# Sheet1.net
KiCad netlist of a schematic drawn in Altium Designer
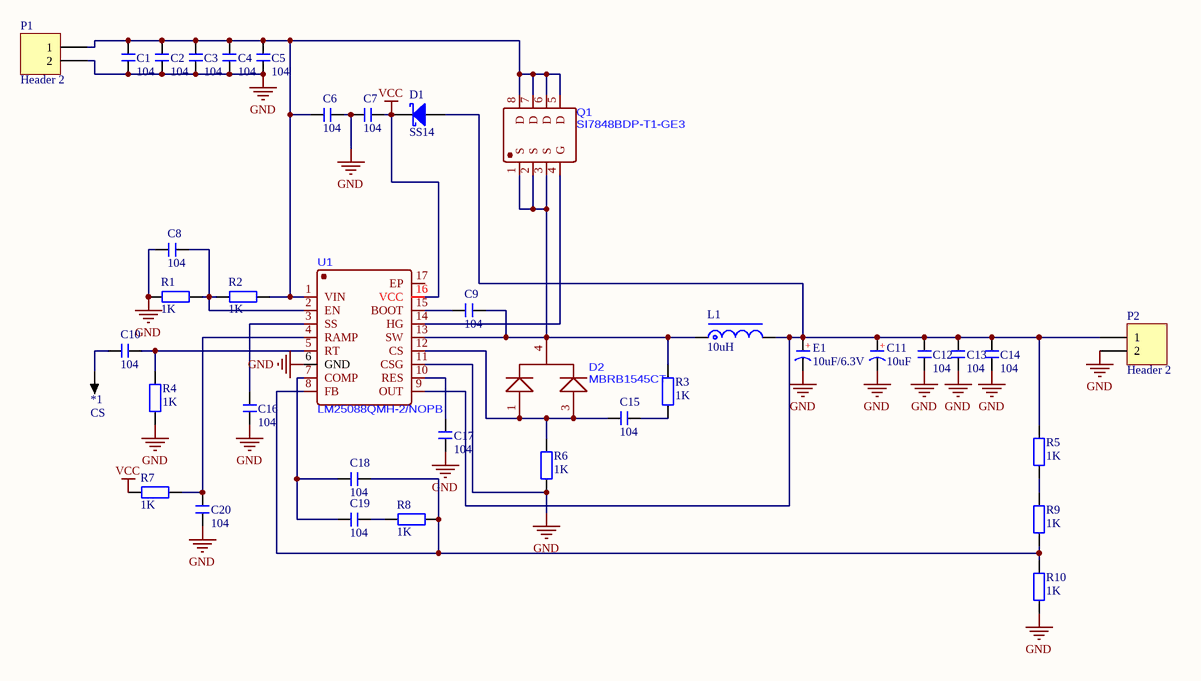
[diagram p0: Sheet1.SchDoc]

(export (version "E")
  (design (tool "Eeschema 10.0.6"))
  (components
    (comp (ref "*1")
      (value "CS")
      (footprint "R100")
      (description "探针焊盘")
      (libsource (lib "10 - 未分类元器件") (part "CS"))
    )
    (comp (ref "C1")
      (value "104")
      (footprint "C 0805_L")
      (description "贴片电容")
      (libsource (lib "01 - 电容-电阻-电感") (part "C"))
    )
    (comp (ref "C2")
      (value "104")
      (footprint "C 0805_L")
      (description "贴片电容")
      (libsource (lib "01 - 电容-电阻-电感") (part "C"))
    )
    (comp (ref "C3")
      (value "104")
      (footprint "C 0805_L")
      (description "贴片电容")
      (libsource (lib "01 - 电容-电阻-电感") (part "C"))
    )
    (comp (ref "C4")
      (value "104")
      (footprint "C 0805_L")
      (description "贴片电容")
      (libsource (lib "01 - 电容-电阻-电感") (part "C"))
    )
    (comp (ref "C5")
      (value "104")
      (footprint "C 0805_L")
      (description "贴片电容")
      (libsource (lib "01 - 电容-电阻-电感") (part "C"))
    )
    (comp (ref "C6")
      (value "104")
      (footprint "C 0805_L")
      (description "贴片电容")
      (libsource (lib "01 - 电容-电阻-电感") (part "C"))
    )
    (comp (ref "C7")
      (value "104")
      (footprint "C 0805_L")
      (description "贴片电容")
      (libsource (lib "01 - 电容-电阻-电感") (part "C"))
    )
    (comp (ref "C8")
      (value "104")
      (footprint "C 0805_L")
      (description "贴片电容")
      (libsource (lib "01 - 电容-电阻-电感") (part "C"))
    )
    (comp (ref "C9")
      (value "104")
      (footprint "C 0805_L")
      (description "贴片电容")
      (libsource (lib "01 - 电容-电阻-电感") (part "C"))
    )
    (comp (ref "C10")
      (value "104")
      (footprint "C 0805_L")
      (description "贴片电容")
      (libsource (lib "01 - 电容-电阻-电感") (part "C"))
    )
    (comp (ref "C11")
      (value "10uF")
      (footprint "CAP 3.5*8*11.5 - BK")
      (description "直插电解电容")
      (libsource (lib "01 - 电容-电阻-电感") (part "CE"))
    )
    (comp (ref "C12")
      (value "104")
      (footprint "C 0805_L")
      (description "贴片电容")
      (libsource (lib "01 - 电容-电阻-电感") (part "C"))
    )
    (comp (ref "C13")
      (value "104")
      (footprint "C 0805_L")
      (description "贴片电容")
      (libsource (lib "01 - 电容-电阻-电感") (part "C"))
    )
    (comp (ref "C14")
      (value "104")
      (footprint "C 0805_L")
      (description "贴片电容")
      (libsource (lib "01 - 电容-电阻-电感") (part "C"))
    )
    (comp (ref "C15")
      (value "104")
      (footprint "C 0805_L")
      (description "贴片电容")
      (libsource (lib "01 - 电容-电阻-电感") (part "C"))
    )
    (comp (ref "C16")
      (value "104")
      (footprint "C 0805_L")
      (description "贴片电容")
      (libsource (lib "01 - 电容-电阻-电感") (part "C"))
    )
    (comp (ref "C17")
      (value "104")
      (footprint "C 0805_L")
      (description "贴片电容")
      (libsource (lib "01 - 电容-电阻-电感") (part "C"))
    )
    (comp (ref "C18")
      (value "104")
      (footprint "C 0805_L")
      (description "贴片电容")
      (libsource (lib "01 - 电容-电阻-电感") (part "C"))
    )
    (comp (ref "C19")
      (value "104")
      (footprint "C 0805_L")
      (description "贴片电容")
      (libsource (lib "01 - 电容-电阻-电感") (part "C"))
    )
    (comp (ref "C20")
      (value "104")
      (footprint "C 0805_L")
      (description "贴片电容")
      (libsource (lib "01 - 电容-电阻-电感") (part "C"))
    )
    (comp (ref "D1")
      (value "SS14")
      (footprint "SMA")
      (description "肖特基二极管")
      (libsource (lib "02 - 二极管(LED)-三极管-整流桥") (part "SS14"))
    )
    (comp (ref "D2")
      (value "MBRB1545CT")
      (footprint "ONSC-D2PAK-3-418B-04_V")
      (libsource (lib "MBRB1545CT_2022-06-29") (part "MBRB1545CT"))
    )
    (comp (ref "E1")
      (value "10uF/6.3V")
      (footprint "CS 2.0*5*8 - C")
      (description "直插固态电容")
      (libsource (lib "01 - 电容-电阻-电感") (part "CS"))
    )
    (comp (ref "L1")
      (value "10uH")
      (footprint "CD31")
      (description "CD系列贴片线绕功率电感")
      (libsource (lib "01 - 电容-电阻-电感") (part "L-SMD"))
    )
    (comp (ref "P1")
      (value "Header 2")
      (footprint "HDR1X2")
      (description "Header, 2-Pin")
      (fields (field (name "PUBLISHER") "Altium Limited"))
      (libsource (lib "") (part "Header 2_1"))
    )
    (comp (ref "P2")
      (value "Header 2")
      (footprint "HDR1X2")
      (description "Header, 2-Pin")
      (fields (field (name "PUBLISHER") "Altium Limited"))
      (libsource (lib "Miscellaneous Connectors") (part "Header 2"))
    )
    (comp (ref "Q1")
      (value "SI7848BDP-T1-GE3")
      (footprint "POWERPAK-SO-8_L6.1-W5.1-P1.27-BL-EP")
      (libsource (lib "SI7848BDP-T1-GE3_2022-06-29") (part "SI7848BDP-T1-GE3"))
    )
    (comp (ref "R1")
      (value "1K")
      (footprint "R 0805_L")
      (description "贴片电阻")
      (libsource (lib "01 - 电容-电阻-电感") (part "R"))
    )
    (comp (ref "R2")
      (value "1K")
      (footprint "R 0805_L")
      (description "贴片电阻")
      (libsource (lib "01 - 电容-电阻-电感") (part "R"))
    )
    (comp (ref "R3")
      (value "1K")
      (footprint "R 0805_L")
      (description "贴片电阻")
      (libsource (lib "01 - 电容-电阻-电感") (part "R"))
    )
    (comp (ref "R4")
      (value "1K")
      (footprint "R 0805_L")
      (description "贴片电阻")
      (libsource (lib "01 - 电容-电阻-电感") (part "R"))
    )
    (comp (ref "R5")
      (value "1K")
      (footprint "R 0805_L")
      (description "贴片电阻")
      (libsource (lib "01 - 电容-电阻-电感") (part "R"))
    )
    (comp (ref "R6")
      (value "1K")
      (footprint "R 0805_L")
      (description "贴片电阻")
      (libsource (lib "01 - 电容-电阻-电感") (part "R"))
    )
    (comp (ref "R7")
      (value "1K")
      (footprint "R 0805_L")
      (description "贴片电阻")
      (libsource (lib "01 - 电容-电阻-电感") (part "R"))
    )
    (comp (ref "R8")
      (value "1K")
      (footprint "R 0805_L")
      (description "贴片电阻")
      (libsource (lib "01 - 电容-电阻-电感") (part "R"))
    )
    (comp (ref "R9")
      (value "1K")
      (footprint "R 0805_L")
      (description "贴片电阻")
      (libsource (lib "01 - 电容-电阻-电感") (part "R"))
    )
    (comp (ref "R10")
      (value "1K")
      (footprint "R 0805_L")
      (description "贴片电阻")
      (libsource (lib "01 - 电容-电阻-电感") (part "R"))
    )
    (comp (ref "U1")
      (value "LM25088QMH-2/NOPB")
      (footprint "HTSSOP-16_L5.0-W4.4-P0.65-LS6.4-BL-EP")
      (libsource (lib "PCB_Project") (part "LM25088QMH-2/NOPB"))
    )
  )
  (nets
    (net (code "1") (name "GND") (class "Default")
      (node (ref "C1") (pin "1") (pinfunction "1_1") (pintype "passive"))
      (node (ref "C11") (pin "2") (pinfunction "K_2") (pintype "passive"))
      (node (ref "C12") (pin "2") (pinfunction "2_2") (pintype "passive"))
      (node (ref "C13") (pin "2") (pinfunction "2_2") (pintype "passive"))
      (node (ref "C14") (pin "2") (pinfunction "2_2") (pintype "passive"))
      (node (ref "C16") (pin "2") (pinfunction "2_2") (pintype "passive"))
      (node (ref "C17") (pin "2") (pinfunction "2_2") (pintype "passive"))
      (node (ref "C2") (pin "1") (pinfunction "1_1") (pintype "passive"))
      (node (ref "C20") (pin "2") (pinfunction "2_2") (pintype "passive"))
      (node (ref "C3") (pin "1") (pinfunction "1_1") (pintype "passive"))
      (node (ref "C4") (pin "1") (pinfunction "1_1") (pintype "passive"))
      (node (ref "C5") (pin "1") (pinfunction "1_1") (pintype "passive"))
      (node (ref "C6") (pin "1") (pinfunction "1_1") (pintype "passive"))
      (node (ref "C7") (pin "2") (pinfunction "2_2") (pintype "passive"))
      (node (ref "C8") (pin "2") (pinfunction "2_2") (pintype "passive"))
      (node (ref "E1") (pin "2") (pinfunction "K_2") (pintype "passive"))
      (node (ref "P1") (pin "2") (pinfunction "2_2") (pintype "passive"))
      (node (ref "P2") (pin "2") (pinfunction "2_2") (pintype "passive"))
      (node (ref "R1") (pin "1") (pinfunction "1_1") (pintype "passive"))
      (node (ref "R10") (pin "1") (pinfunction "1_1") (pintype "passive"))
      (node (ref "R4") (pin "1") (pinfunction "1_1") (pintype "passive"))
      (node (ref "R6") (pin "1") (pinfunction "1_1") (pintype "passive"))
      (node (ref "U1") (pin "11") (pinfunction "CSG_11") (pintype "passive"))
      (node (ref "U1") (pin "6") (pinfunction "GND_6") (pintype "passive"))
    )
    (net (code "2") (name "Net-(*1-Pad1)") (class "Default")
      (node (ref "*1") (pin "1") (pinfunction "1_1") (pintype "passive"))
      (node (ref "C10") (pin "2") (pinfunction "2_2") (pintype "passive"))
    )
    (net (code "3") (name "Net-(C11-A)") (class "Default")
      (node (ref "C11") (pin "1") (pinfunction "A_1") (pintype "passive"))
      (node (ref "C12") (pin "1") (pinfunction "1_1") (pintype "passive"))
      (node (ref "C13") (pin "1") (pinfunction "1_1") (pintype "passive"))
      (node (ref "C14") (pin "1") (pinfunction "1_1") (pintype "passive"))
      (node (ref "D1") (pin "1") (pinfunction "A_1") (pintype "passive"))
      (node (ref "E1") (pin "1") (pinfunction "A_1") (pintype "passive"))
      (node (ref "L1") (pin "2") (pinfunction "2_2") (pintype "passive"))
      (node (ref "P2") (pin "1") (pinfunction "1_1") (pintype "passive"))
      (node (ref "R5") (pin "2") (pinfunction "2_2") (pintype "passive"))
      (node (ref "U1") (pin "9") (pinfunction "OUT_9") (pintype "passive"))
    )
    (net (code "4") (name "Net-(C15-Pad1)") (class "Default")
      (node (ref "C15") (pin "1") (pinfunction "1_1") (pintype "passive"))
      (node (ref "R3") (pin "1") (pinfunction "1_1") (pintype "passive"))
    )
    (net (code "5") (name "Net-(C19-Pad2)") (class "Default")
      (node (ref "C19") (pin "2") (pinfunction "2_2") (pintype "passive"))
      (node (ref "R8") (pin "2") (pinfunction "2_2") (pintype "passive"))
    )
    (net (code "6") (name "Net-(D2-A1)") (class "Default")
      (node (ref "C15") (pin "2") (pinfunction "2_2") (pintype "passive"))
      (node (ref "D2") (pin "1") (pinfunction "A1_1") (pintype "passive"))
      (node (ref "D2") (pin "3") (pinfunction "A2_3") (pintype "passive"))
      (node (ref "R6") (pin "2") (pinfunction "2_2") (pintype "passive"))
      (node (ref "U1") (pin "12") (pinfunction "CS_12") (pintype "passive"))
    )
    (net (code "7") (name "Net-(D2-K)") (class "Default")
      (node (ref "C9") (pin "1") (pinfunction "1_1") (pintype "passive"))
      (node (ref "D2") (pin "4") (pinfunction "K_4") (pintype "passive"))
      (node (ref "L1") (pin "1") (pinfunction "1_1") (pintype "passive"))
      (node (ref "Q1") (pin "1") (pinfunction "S_1") (pintype "passive"))
      (node (ref "Q1") (pin "2") (pinfunction "S_2") (pintype "passive"))
      (node (ref "Q1") (pin "3") (pinfunction "S_3") (pintype "passive"))
      (node (ref "R3") (pin "2") (pinfunction "2_2") (pintype "passive"))
      (node (ref "U1") (pin "13") (pinfunction "SW_13") (pintype "passive"))
    )
    (net (code "8") (name "Net-(Q1-G)") (class "Default")
      (node (ref "Q1") (pin "4") (pinfunction "G_4") (pintype "passive"))
      (node (ref "U1") (pin "14") (pinfunction "HG_14") (pintype "passive"))
    )
    (net (code "9") (name "Net-(R5-Pad1)") (class "Default")
      (node (ref "R5") (pin "1") (pinfunction "1_1") (pintype "passive"))
      (node (ref "R9") (pin "2") (pinfunction "2_2") (pintype "passive"))
    )
    (net (code "10") (name "Net-(U1-BOOT)") (class "Default")
      (node (ref "C9") (pin "2") (pinfunction "2_2") (pintype "passive"))
      (node (ref "U1") (pin "15") (pinfunction "BOOT_15") (pintype "passive"))
    )
    (net (code "11") (name "Net-(U1-COMP)") (class "Default")
      (node (ref "C18") (pin "1") (pinfunction "1_1") (pintype "passive"))
      (node (ref "C19") (pin "1") (pinfunction "1_1") (pintype "passive"))
      (node (ref "U1") (pin "7") (pinfunction "COMP_7") (pintype "passive"))
    )
    (net (code "12") (name "Net-(U1-EN)") (class "Default")
      (node (ref "C8") (pin "1") (pinfunction "1_1") (pintype "passive"))
      (node (ref "R1") (pin "2") (pinfunction "2_2") (pintype "passive"))
      (node (ref "R2") (pin "1") (pinfunction "1_1") (pintype "passive"))
      (node (ref "U1") (pin "2") (pinfunction "EN_2") (pintype "passive"))
    )
    (net (code "13") (name "Net-(U1-FB)") (class "Default")
      (node (ref "C18") (pin "2") (pinfunction "2_2") (pintype "passive"))
      (node (ref "R10") (pin "2") (pinfunction "2_2") (pintype "passive"))
      (node (ref "R8") (pin "1") (pinfunction "1_1") (pintype "passive"))
      (node (ref "R9") (pin "1") (pinfunction "1_1") (pintype "passive"))
      (node (ref "U1") (pin "8") (pinfunction "FB_8") (pintype "passive"))
    )
    (net (code "14") (name "Net-(U1-RAMP)") (class "Default")
      (node (ref "C20") (pin "1") (pinfunction "1_1") (pintype "passive"))
      (node (ref "R7") (pin "2") (pinfunction "2_2") (pintype "passive"))
      (node (ref "U1") (pin "4") (pinfunction "RAMP_4") (pintype "passive"))
    )
    (net (code "15") (name "Net-(U1-RES)") (class "Default")
      (node (ref "C17") (pin "1") (pinfunction "1_1") (pintype "passive"))
      (node (ref "U1") (pin "10") (pinfunction "RES_10") (pintype "passive"))
    )
    (net (code "16") (name "Net-(U1-RT)") (class "Default")
      (node (ref "C10") (pin "1") (pinfunction "1_1") (pintype "passive"))
      (node (ref "R4") (pin "2") (pinfunction "2_2") (pintype "passive"))
      (node (ref "U1") (pin "5") (pinfunction "RT_5") (pintype "passive"))
    )
    (net (code "17") (name "Net-(U1-SS)") (class "Default")
      (node (ref "C16") (pin "1") (pinfunction "1_1") (pintype "passive"))
      (node (ref "U1") (pin "3") (pinfunction "SS_3") (pintype "passive"))
    )
    (net (code "18") (name "Net-(U1-VIN)") (class "Default")
      (node (ref "C1") (pin "2") (pinfunction "2_2") (pintype "passive"))
      (node (ref "C2") (pin "2") (pinfunction "2_2") (pintype "passive"))
      (node (ref "C3") (pin "2") (pinfunction "2_2") (pintype "passive"))
      (node (ref "C4") (pin "2") (pinfunction "2_2") (pintype "passive"))
      (node (ref "C5") (pin "2") (pinfunction "2_2") (pintype "passive"))
      (node (ref "C6") (pin "2") (pinfunction "2_2") (pintype "passive"))
      (node (ref "P1") (pin "1") (pinfunction "1_1") (pintype "passive"))
      (node (ref "Q1") (pin "5") (pinfunction "D_5") (pintype "passive"))
      (node (ref "Q1") (pin "6") (pinfunction "D_6") (pintype "passive"))
      (node (ref "Q1") (pin "7") (pinfunction "D_7") (pintype "passive"))
      (node (ref "Q1") (pin "8") (pinfunction "D_8") (pintype "passive"))
      (node (ref "R2") (pin "2") (pinfunction "2_2") (pintype "passive"))
      (node (ref "U1") (pin "1") (pinfunction "VIN_1") (pintype "passive"))
    )
    (net (code "19") (name "VCC") (class "Default")
      (node (ref "C7") (pin "1") (pinfunction "1_1") (pintype "passive"))
      (node (ref "D1") (pin "2") (pinfunction "K_2") (pintype "passive"))
      (node (ref "R7") (pin "1") (pinfunction "1_1") (pintype "passive"))
      (node (ref "U1") (pin "16") (pinfunction "VCC_16") (pintype "passive"))
    )
    (net (code "20") (name "unconnected-(U1-EP-Pad17)") (class "Default")
      (node (ref "U1") (pin "17") (pinfunction "EP_17") (pintype "passive"))
    )
  )
)
